# POWER.net
KiCad netlist of a schematic drawn in Altium Designer
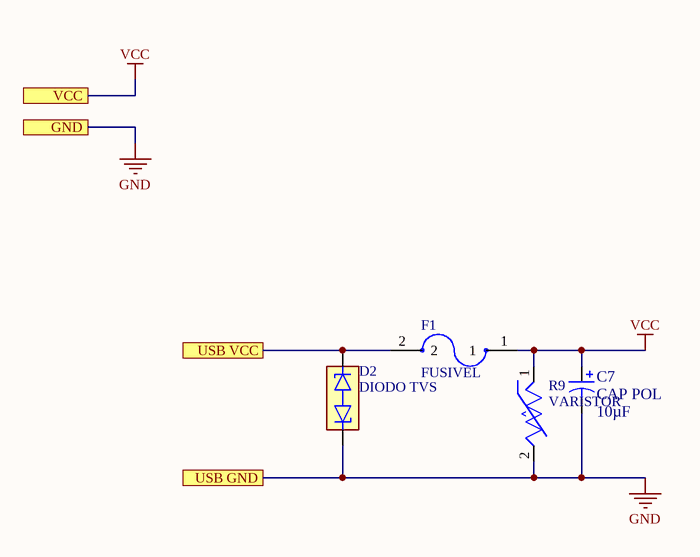
[diagram p0: POWER.SchDoc]

(export (version "E")
  (design (tool "Eeschema 10.0.6"))
  (components
    (comp (ref "C7")
      (value "CAP POL")
      (footprint "CONDENS 10uF")
      (description "Polarized Capacitor (Axial)")
      (fields (field (name "ALTIUM_VALUE") "10µF") (field (name "PUBLISHER") "Altium Limited"))
      (libsource (lib "MySchem") (part "Cap Pol2"))
    )
    (comp (ref "D2")
      (value "DIODO TVS")
      (footprint "DIODO TVS")
      (description "1 Amp General Purpose Rectifier")
      (fields (field (name "PUBLISHER") "Altium Limited"))
      (libsource (lib "MySchem") (part "DIODO TVS"))
    )
    (comp (ref "F1")
      (value "FUSIVEL")
      (footprint "FUSIVEL ARMADO 0.5A")
      (description "Fuse")
      (fields (field (name "PUBLISHER") "Altium Limited"))
      (libsource (lib "MySchem") (part "FUSIVEL ARMADO 0.5A"))
    )
    (comp (ref "R9")
      (value "VARISTOR")
      (footprint "VARISTOR")
      (description "Varistor (Voltage-Sensitive Resistor)")
      (fields (field (name "PUBLISHER") "Altium Limited"))
      (libsource (lib "MySchem") (part "VARISTOR"))
    )
  )
  (nets
    (net (code "1") (name "/USB VCC") (class "Default")
      (node (ref "D2") (pin "2") (pinfunction "2_2") (pintype "passive"))
      (node (ref "F1") (pin "2") (pinfunction "2_2") (pintype "passive"))
    )
    (net (code "2") (name "GND") (class "Default")
      (node (ref "C7") (pin "2") (pinfunction "2_2") (pintype "passive"))
      (node (ref "D2") (pin "1") (pinfunction "1_1") (pintype "passive"))
      (node (ref "R9") (pin "2") (pinfunction "2_2") (pintype "passive"))
    )
    (net (code "3") (name "VCC") (class "Default")
      (node (ref "C7") (pin "1") (pinfunction "1_1") (pintype "passive"))
      (node (ref "F1") (pin "1") (pinfunction "1_1") (pintype "passive"))
      (node (ref "R9") (pin "1") (pinfunction "1_1") (pintype "passive"))
    )
  )
)
